# Microcontroller.net
KiCad netlist of a schematic drawn in Altium Designer
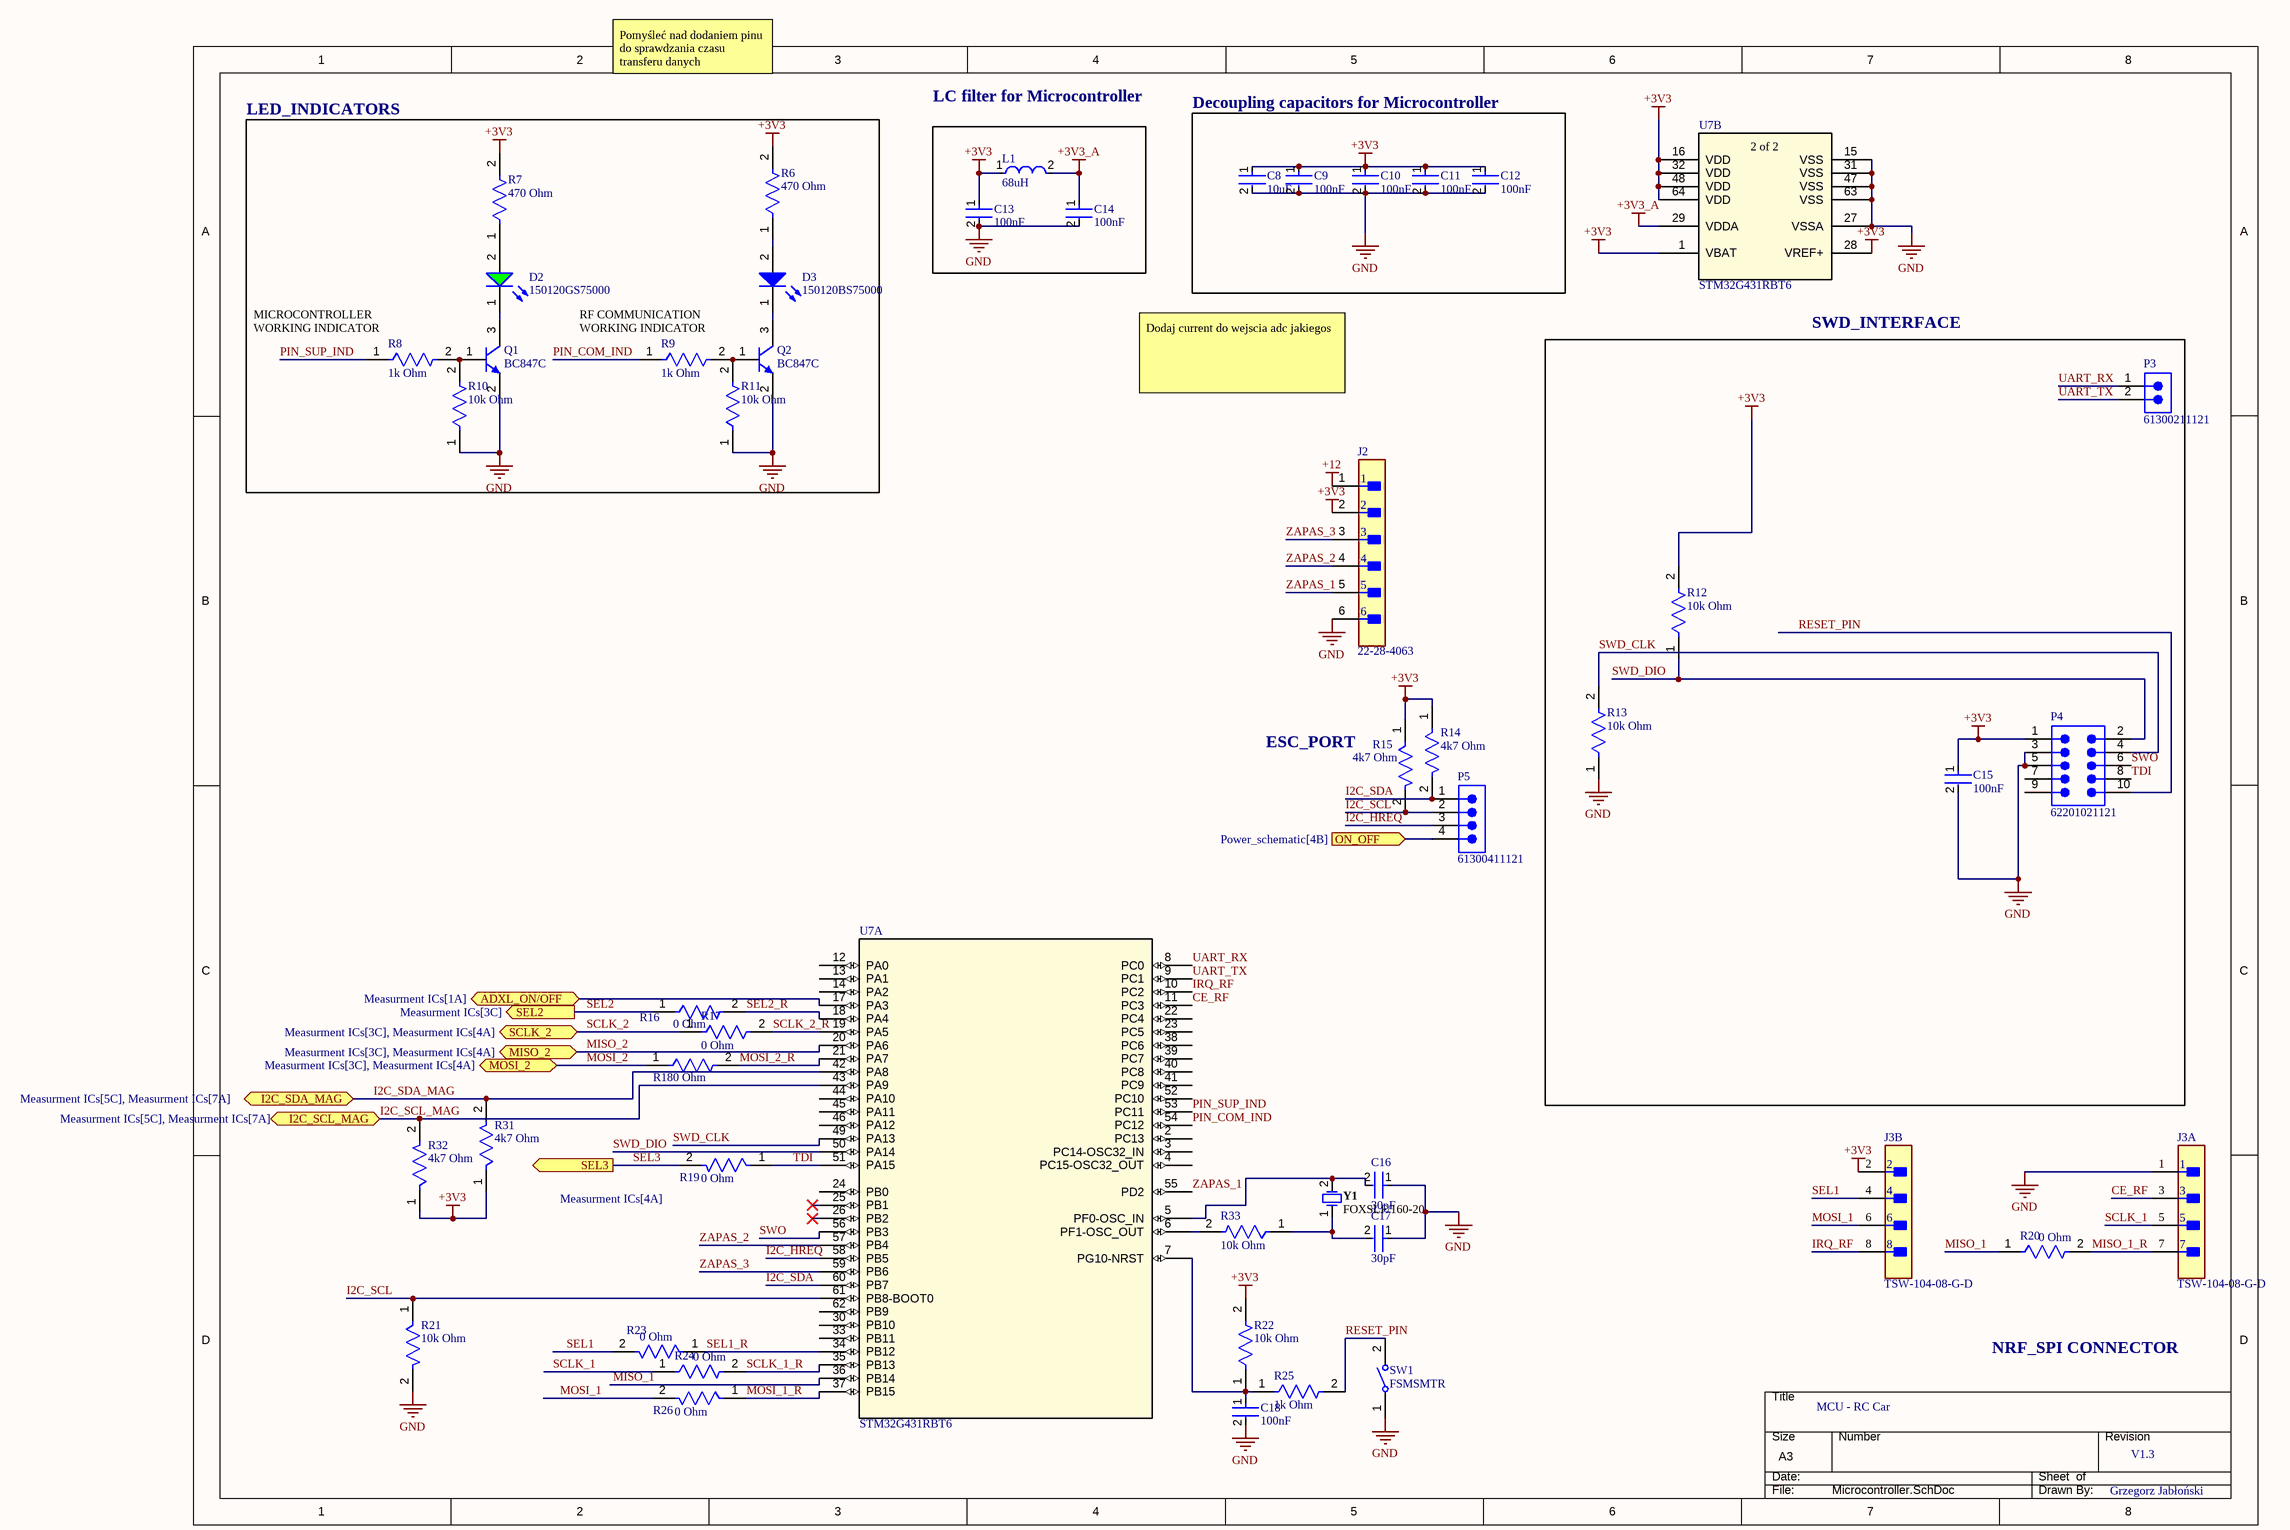
[diagram p0: Microcontroller.SchDoc]

(export (version "E")
  (design (tool "Eeschema 10.0.6"))
  (components
    (comp (ref "C8")
      (value "10uF")
      (footprint "FP-CC0805-0_85-MFG")
      (description "CAP CER 0.1UF 50V X7R 0805")
      (fields (field (name "TOLERANCE") "0.1") (field (name "MANUFACTURER PART NUMBER") "CC0805KRX7R9BB104"))
      (libsource (lib "Altium Content Vault") (part "11868f565c42a9108669ba33697ecf6"))
    )
    (comp (ref "C9")
      (value "100nF")
      (footprint "FP-CC0805-0_85-MFG")
      (description "CAP CER 0.1UF 50V X7R 0805")
      (fields (field (name "TOLERANCE") "0.1") (field (name "MANUFACTURER PART NUMBER") "CC0805KRX7R9BB104"))
      (libsource (lib "Altium Content Vault") (part "11868f565c42a9108669ba33697ecf6"))
    )
    (comp (ref "C10")
      (value "100nF")
      (footprint "FP-CC0805-0_85-MFG")
      (description "CAP CER 0.1UF 50V X7R 0805")
      (fields (field (name "TOLERANCE") "0.1") (field (name "MANUFACTURER PART NUMBER") "CC0805KRX7R9BB104"))
      (libsource (lib "Altium Content Vault") (part "11868f565c42a9108669ba33697ecf6"))
    )
    (comp (ref "C11")
      (value "100nF")
      (footprint "FP-CC0805-0_85-MFG")
      (description "CAP CER 0.1UF 50V X7R 0805")
      (fields (field (name "TOLERANCE") "0.1") (field (name "MANUFACTURER PART NUMBER") "CC0805KRX7R9BB104"))
      (libsource (lib "Altium Content Vault") (part "11868f565c42a9108669ba33697ecf6"))
    )
    (comp (ref "C12")
      (value "100nF")
      (footprint "FP-CC0805-0_85-MFG")
      (description "CAP CER 0.1UF 50V X7R 0805")
      (fields (field (name "TOLERANCE") "0.1") (field (name "MANUFACTURER PART NUMBER") "CC0805KRX7R9BB104"))
      (libsource (lib "Altium Content Vault") (part "11868f565c42a9108669ba33697ecf6"))
    )
    (comp (ref "C13")
      (value "100nF")
      (footprint "FP-CC0805-0_85-MFG")
      (description "CAP CER 0.1UF 50V X7R 0805")
      (fields (field (name "TOLERANCE") "0.1") (field (name "MANUFACTURER PART NUMBER") "CC0805KRX7R9BB104"))
      (libsource (lib "Altium Content Vault") (part "11868f565c42a9108669ba33697ecf6"))
    )
    (comp (ref "C14")
      (value "100nF")
      (footprint "FP-CC0805-0_85-MFG")
      (description "CAP CER 0.1UF 50V X7R 0805")
      (fields (field (name "TOLERANCE") "0.1") (field (name "MANUFACTURER PART NUMBER") "CC0805KRX7R9BB104"))
      (libsource (lib "Altium Content Vault") (part "11868f565c42a9108669ba33697ecf6"))
    )
    (comp (ref "C15")
      (value "100nF")
      (footprint "FP-CC0805-0_85-MFG")
      (description "CAP CER 0.1UF 50V X7R 0805")
      (fields (field (name "TOLERANCE") "0.1") (field (name "MANUFACTURER PART NUMBER") "CC0805KRX7R9BB104"))
      (libsource (lib "Altium Content Vault") (part "11868f565c42a9108669ba33697ecf6"))
    )
    (comp (ref "C16")
      (value "30pF")
      (footprint "FP-CC0805-0_85-MFG")
      (description "CAP CER 0.1UF 50V X7R 0805")
      (fields (field (name "TOLERANCE") "0.1") (field (name "MANUFACTURER PART NUMBER") "CC0805KRX7R9BB104"))
      (libsource (lib "Altium Content Vault") (part "11868f565c42a9108669ba33697ecf6"))
    )
    (comp (ref "C17")
      (value "30pF")
      (footprint "FP-CC0805-0_85-MFG")
      (description "CAP CER 0.1UF 50V X7R 0805")
      (fields (field (name "TOLERANCE") "0.1") (field (name "MANUFACTURER PART NUMBER") "CC0805KRX7R9BB104"))
      (libsource (lib "Altium Content Vault") (part "11868f565c42a9108669ba33697ecf6"))
    )
    (comp (ref "C18")
      (value "100nF")
      (footprint "FP-CC0805-0_85-MFG")
      (description "CAP CER 0.1UF 50V X7R 0805")
      (fields (field (name "TOLERANCE") "0.1") (field (name "MANUFACTURER PART NUMBER") "CC0805KRX7R9BB104"))
      (libsource (lib "Altium Content Vault") (part "11868f565c42a9108669ba33697ecf6"))
    )
    (comp (ref "D2")
      (value "150120GS75000")
      (footprint "WL-SMCW_1206_150120xx75000")
      (description "WL-SMCW SMT Mono-Color Chip LED Waterclear")
      (libsource (lib "Altium Content Vault") (part "LED_Green_2A-1K"))
    )
    (comp (ref "D3")
      (value "150120BS75000")
      (footprint "WL-SMCW_1206_150120xx75000")
      (description "WL-SMCW SMT Mono-Color Chip LED Waterclear")
      (libsource (lib "Altium Content Vault") (part "LED_Blue_2A-1K"))
    )
    (comp (ref "J2")
      (value "22-28-4063")
      (footprint "FP-22-28-4063-MFG")
      (description "CONN HEADER VERT 6POS 2.54MM")
      (libsource (lib "Altium Content Vault") (part "f2cb566baf1c37ab5a3b8e90bbeafd6"))
    )
    (comp (ref "J3")
      (value "TSW-104-08-G-D")
      (footprint "FP-TSW-104-08-G-D-MFG")
      (libsource (lib "Altium Content Vault") (part "811e954b9c034aa737de4d9295cbe7e"))
    )
    (comp (ref "L1")
      (value "68uH")
      (footprint "FP-CB2518-MFG")
      (description "SMD Inductors 68uH ±10% 0.31A 1.95Ω 1007")
      (fields (field (name "TOLERANCE") "10%"))
      (libsource (lib "Altium Content Vault") (part "725321dda6339637d4d059423bc1c3c"))
    )
    (comp (ref "P3")
      (value "61300211121")
      (footprint "61300211121")
      (libsource (lib "Altium Content Vault") (part "Header_Male_1R_02P"))
    )
    (comp (ref "P4")
      (value "62201021121")
      (footprint "62201021121")
      (libsource (lib "Altium Content Vault") (part "Header_Male_2R_10P"))
    )
    (comp (ref "P5")
      (value "61300411121")
      (footprint "61300411121")
      (libsource (lib "Altium Content Vault") (part "Header_Male_1R_04P"))
    )
    (comp (ref "Q1")
      (value "BC847C")
      (footprint "INF-SOT23_L")
      (description "NPN Silicon AF Transistor, 45 V VCEO, 100 mA IC, SOT23, Reel, Green")
      (fields (field (name "MANUFACTURER") "Infineon"))
      (libsource (lib "Altium Content Vault") (part "INF-BJTNPN-BEC-3"))
    )
    (comp (ref "Q2")
      (value "BC847C")
      (footprint "INF-SOT23_L")
      (description "NPN Silicon AF Transistor, 45 V VCEO, 100 mA IC, SOT23, Reel, Green")
      (fields (field (name "MANUFACTURER") "Infineon"))
      (libsource (lib "Altium Content Vault") (part "INF-BJTNPN-BEC-3"))
    )
    (comp (ref "R6")
      (value "470 Ohm")
      (footprint "FP-RMCF0805-MFG")
      (description "RES 0 OHM JUMPER 1/8W 0805")
      (libsource (lib "Altium Content Vault") (part "1029c3af85768c4190bb7ad29bc67b5"))
    )
    (comp (ref "R7")
      (value "470 Ohm")
      (footprint "FP-RMCF0805-MFG")
      (description "RES 0 OHM JUMPER 1/8W 0805")
      (libsource (lib "Altium Content Vault") (part "1029c3af85768c4190bb7ad29bc67b5"))
    )
    (comp (ref "R8")
      (value "1k Ohm")
      (footprint "FP-RMCF0805-MFG")
      (description "RES 0 OHM JUMPER 1/8W 0805")
      (libsource (lib "Altium Content Vault") (part "1029c3af85768c4190bb7ad29bc67b5"))
    )
    (comp (ref "R9")
      (value "1k Ohm")
      (footprint "FP-RMCF0805-MFG")
      (description "RES 0 OHM JUMPER 1/8W 0805")
      (libsource (lib "Altium Content Vault") (part "1029c3af85768c4190bb7ad29bc67b5"))
    )
    (comp (ref "R10")
      (value "10k Ohm")
      (footprint "FP-RMCF0805-MFG")
      (description "RES 0 OHM JUMPER 1/8W 0805")
      (libsource (lib "Altium Content Vault") (part "1029c3af85768c4190bb7ad29bc67b5"))
    )
    (comp (ref "R11")
      (value "10k Ohm")
      (footprint "FP-RMCF0805-MFG")
      (description "RES 0 OHM JUMPER 1/8W 0805")
      (libsource (lib "Altium Content Vault") (part "1029c3af85768c4190bb7ad29bc67b5"))
    )
    (comp (ref "R12")
      (value "10k Ohm")
      (footprint "FP-RMCF0805-MFG")
      (description "RES 0 OHM JUMPER 1/8W 0805")
      (libsource (lib "Altium Content Vault") (part "1029c3af85768c4190bb7ad29bc67b5"))
    )
    (comp (ref "R13")
      (value "10k Ohm")
      (footprint "FP-RMCF0805-MFG")
      (description "RES 0 OHM JUMPER 1/8W 0805")
      (libsource (lib "Altium Content Vault") (part "1029c3af85768c4190bb7ad29bc67b5"))
    )
    (comp (ref "R14")
      (value "4k7 Ohm")
      (footprint "FP-RMCF0805-MFG")
      (description "RES 0 OHM JUMPER 1/8W 0805")
      (libsource (lib "Altium Content Vault") (part "1029c3af85768c4190bb7ad29bc67b5"))
    )
    (comp (ref "R15")
      (value "4k7 Ohm")
      (footprint "FP-RMCF0805-MFG")
      (description "RES 0 OHM JUMPER 1/8W 0805")
      (libsource (lib "Altium Content Vault") (part "1029c3af85768c4190bb7ad29bc67b5"))
    )
    (comp (ref "R16")
      (value "0 Ohm")
      (footprint "FP-RMCF0805-MFG")
      (description "RES 0 OHM JUMPER 1/8W 0805")
      (libsource (lib "Altium Content Vault") (part "1029c3af85768c4190bb7ad29bc67b5"))
    )
    (comp (ref "R17")
      (value "0 Ohm")
      (footprint "FP-RMCF0805-MFG")
      (description "RES 0 OHM JUMPER 1/8W 0805")
      (libsource (lib "Altium Content Vault") (part "1029c3af85768c4190bb7ad29bc67b5"))
    )
    (comp (ref "R18")
      (value "0 Ohm")
      (footprint "FP-RMCF0805-MFG")
      (description "RES 0 OHM JUMPER 1/8W 0805")
      (libsource (lib "Altium Content Vault") (part "1029c3af85768c4190bb7ad29bc67b5"))
    )
    (comp (ref "R19")
      (value "0 Ohm")
      (footprint "FP-RMCF0805-MFG")
      (description "RES 0 OHM JUMPER 1/8W 0805")
      (libsource (lib "Altium Content Vault") (part "1029c3af85768c4190bb7ad29bc67b5"))
    )
    (comp (ref "R20")
      (value "0 Ohm")
      (footprint "FP-RMCF0805-MFG")
      (description "RES 0 OHM JUMPER 1/8W 0805")
      (libsource (lib "Altium Content Vault") (part "1029c3af85768c4190bb7ad29bc67b5"))
    )
    (comp (ref "R21")
      (value "10k Ohm")
      (footprint "FP-RMCF0805-MFG")
      (description "RES 0 OHM JUMPER 1/8W 0805")
      (libsource (lib "Altium Content Vault") (part "1029c3af85768c4190bb7ad29bc67b5"))
    )
    (comp (ref "R22")
      (value "10k Ohm")
      (footprint "FP-RMCF0805-MFG")
      (description "RES 0 OHM JUMPER 1/8W 0805")
      (libsource (lib "Altium Content Vault") (part "1029c3af85768c4190bb7ad29bc67b5"))
    )
    (comp (ref "R23")
      (value "0 Ohm")
      (footprint "FP-RMCF0805-MFG")
      (description "RES 0 OHM JUMPER 1/8W 0805")
      (libsource (lib "Altium Content Vault") (part "1029c3af85768c4190bb7ad29bc67b5"))
    )
    (comp (ref "R24")
      (value "0 Ohm")
      (footprint "FP-RMCF0805-MFG")
      (description "RES 0 OHM JUMPER 1/8W 0805")
      (libsource (lib "Altium Content Vault") (part "1029c3af85768c4190bb7ad29bc67b5"))
    )
    (comp (ref "R25")
      (value "1k Ohm")
      (footprint "FP-RMCF0805-MFG")
      (description "RES 0 OHM JUMPER 1/8W 0805")
      (libsource (lib "Altium Content Vault") (part "1029c3af85768c4190bb7ad29bc67b5"))
    )
    (comp (ref "R26")
      (value "0 Ohm")
      (footprint "FP-RMCF0805-MFG")
      (description "RES 0 OHM JUMPER 1/8W 0805")
      (libsource (lib "Altium Content Vault") (part "1029c3af85768c4190bb7ad29bc67b5"))
    )
    (comp (ref "R31")
      (value "4k7 Ohm")
      (footprint "FP-RMCF0805-MFG")
      (description "RES 0 OHM JUMPER 1/8W 0805")
      (libsource (lib "Altium Content Vault") (part "1029c3af85768c4190bb7ad29bc67b5"))
    )
    (comp (ref "R32")
      (value "4k7 Ohm")
      (footprint "FP-RMCF0805-MFG")
      (description "RES 0 OHM JUMPER 1/8W 0805")
      (libsource (lib "Altium Content Vault") (part "1029c3af85768c4190bb7ad29bc67b5"))
    )
    (comp (ref "R33")
      (value "10k Ohm")
      (footprint "FP-RMCF0805-MFG")
      (description "RES 0 OHM JUMPER 1/8W 0805")
      (libsource (lib "Altium Content Vault") (part "1029c3af85768c4190bb7ad29bc67b5"))
    )
    (comp (ref "SW1")
      (value "FSMSMTR")
      (footprint "TECO-FSMSMTR_V")
      (description "FSMSM Push Button Switch, 50 mA, -35 to 85 degC, 2-Pin SMD, RoHS, Tape and Reel")
      (fields (field (name "MANUFACTURER") "TE Connectivity"))
      (libsource (lib "Altium Content Vault") (part "SW-SPST-2_C"))
    )
    (comp (ref "U7")
      (value "STM32G431RBT6")
      (footprint "LQFP64-10x10mm")
      (description "No Description Available")
      (libsource (lib "STM32G431RBT6") (part "STM32G431RBT6"))
    )
    (comp (ref "Y1")
      (value "FOXSLF/160-20")
      (footprint "FOX-FOXSLF160-20")
      (description "Resistance Weld Thru-Hole Crystal, 16 MHz, -20 to 70 degC, 2-Pin THD, RoHS, Bulk")
      (fields (field (name "TOLERANCE") "1%"))
      (libsource (lib "Altium Content Vault") (part "XTAL-1-2-2"))
    )
  )
  (nets
    (net (code "1") (name "+3V3") (class "Default")
      (node (ref "C10") (pin "1") (pinfunction "1_1") (pintype "passive"))
      (node (ref "C11") (pin "1") (pinfunction "1_1") (pintype "passive"))
      (node (ref "C12") (pin "1") (pinfunction "1_1") (pintype "passive"))
      (node (ref "C13") (pin "1") (pinfunction "1_1") (pintype "passive"))
      (node (ref "C15") (pin "1") (pinfunction "1_1") (pintype "passive"))
      (node (ref "C8") (pin "1") (pinfunction "1_1") (pintype "passive"))
      (node (ref "C9") (pin "1") (pinfunction "1_1") (pintype "passive"))
      (node (ref "J2") (pin "2") (pinfunction "2_2") (pintype "passive"))
      (node (ref "J3") (pin "2") (pinfunction "2_2") (pintype "passive"))
      (node (ref "L1") (pin "1") (pinfunction "1_1") (pintype "passive"))
      (node (ref "P4") (pin "1") (pinfunction "1_1") (pintype "passive"))
      (node (ref "R12") (pin "2") (pinfunction "2_2") (pintype "passive"))
      (node (ref "R14") (pin "1") (pinfunction "1_1") (pintype "passive"))
      (node (ref "R15") (pin "1") (pinfunction "1_1") (pintype "passive"))
      (node (ref "R22") (pin "2") (pinfunction "2_2") (pintype "passive"))
      (node (ref "R31") (pin "1") (pinfunction "1_1") (pintype "passive"))
      (node (ref "R32") (pin "1") (pinfunction "1_1") (pintype "passive"))
      (node (ref "R6") (pin "2") (pinfunction "2_2") (pintype "passive"))
      (node (ref "R7") (pin "2") (pinfunction "2_2") (pintype "passive"))
      (node (ref "U7") (pin "1") (pinfunction "VBAT_1") (pintype "power_in"))
      (node (ref "U7") (pin "16") (pinfunction "VDD_16") (pintype "power_in"))
      (node (ref "U7") (pin "28") (pinfunction "VREF+_28") (pintype "power_in"))
      (node (ref "U7") (pin "32") (pinfunction "VDD_32") (pintype "power_in"))
      (node (ref "U7") (pin "48") (pinfunction "VDD_48") (pintype "power_in"))
      (node (ref "U7") (pin "64") (pinfunction "VDD_64") (pintype "power_in"))
    )
    (net (code "2") (name "+3V3_A") (class "Default")
      (node (ref "C14") (pin "1") (pinfunction "1_1") (pintype "passive"))
      (node (ref "L1") (pin "2") (pinfunction "2_2") (pintype "passive"))
      (node (ref "U7") (pin "29") (pinfunction "VDDA_29") (pintype "power_in"))
    )
    (net (code "3") (name "+12") (class "Default")
      (node (ref "J2") (pin "1") (pinfunction "1_1") (pintype "passive"))
    )
    (net (code "4") (name "/ADXL_ON{slash}OFF") (class "Default")
      (node (ref "U7") (pin "17") (pinfunction "PA3_17") (pintype "bidirectional"))
    )
    (net (code "5") (name "/CE_RF") (class "Default")
      (node (ref "J3") (pin "3") (pinfunction "3_3") (pintype "passive"))
      (node (ref "U7") (pin "11") (pinfunction "PC3_11") (pintype "bidirectional"))
    )
    (net (code "6") (name "/I2C_HREQ") (class "Default")
      (node (ref "P5") (pin "3") (pinfunction "3_3") (pintype "passive"))
      (node (ref "U7") (pin "58") (pinfunction "PB5_58") (pintype "bidirectional"))
    )
    (net (code "7") (name "/I2C_SCL") (class "Default")
      (node (ref "P5") (pin "2") (pinfunction "2_2") (pintype "passive"))
      (node (ref "R15") (pin "2") (pinfunction "2_2") (pintype "passive"))
      (node (ref "R21") (pin "1") (pinfunction "1_1") (pintype "passive"))
      (node (ref "U7") (pin "61") (pinfunction "PB8-BOOT0_61") (pintype "bidirectional"))
    )
    (net (code "8") (name "/I2C_SCL_MAG") (class "Default")
      (node (ref "R32") (pin "2") (pinfunction "2_2") (pintype "passive"))
      (node (ref "U7") (pin "43") (pinfunction "PA9_43") (pintype "bidirectional"))
    )
    (net (code "9") (name "/I2C_SDA") (class "Default")
      (node (ref "P5") (pin "1") (pinfunction "1_1") (pintype "passive"))
      (node (ref "R14") (pin "2") (pinfunction "2_2") (pintype "passive"))
      (node (ref "U7") (pin "60") (pinfunction "PB7_60") (pintype "bidirectional"))
    )
    (net (code "10") (name "/I2C_SDA_MAG") (class "Default")
      (node (ref "R31") (pin "2") (pinfunction "2_2") (pintype "passive"))
      (node (ref "U7") (pin "42") (pinfunction "PA8_42") (pintype "bidirectional"))
    )
    (net (code "11") (name "/IRQ_RF") (class "Default")
      (node (ref "J3") (pin "8") (pinfunction "8_8") (pintype "passive"))
      (node (ref "U7") (pin "10") (pinfunction "PC2_10") (pintype "bidirectional"))
    )
    (net (code "12") (name "/MISO_1") (class "Default")
      (node (ref "R20") (pin "1") (pinfunction "1_1") (pintype "passive"))
      (node (ref "U7") (pin "36") (pinfunction "PB14_36") (pintype "bidirectional"))
    )
    (net (code "13") (name "/MISO_1_R") (class "Default")
      (node (ref "J3") (pin "7") (pinfunction "7_7") (pintype "passive"))
      (node (ref "R20") (pin "2") (pinfunction "2_2") (pintype "passive"))
    )
    (net (code "14") (name "/MISO_2") (class "Default")
      (node (ref "U7") (pin "20") (pinfunction "PA6_20") (pintype "bidirectional"))
    )
    (net (code "15") (name "/MOSI_1") (class "Default")
      (node (ref "J3") (pin "6") (pinfunction "6_6") (pintype "passive"))
      (node (ref "R26") (pin "2") (pinfunction "2_2") (pintype "passive"))
    )
    (net (code "16") (name "/MOSI_1_R") (class "Default")
      (node (ref "R26") (pin "1") (pinfunction "1_1") (pintype "passive"))
      (node (ref "U7") (pin "37") (pinfunction "PB15_37") (pintype "bidirectional"))
    )
    (net (code "17") (name "/MOSI_2") (class "Default")
      (node (ref "R18") (pin "1") (pinfunction "1_1") (pintype "passive"))
    )
    (net (code "18") (name "/MOSI_2_R") (class "Default")
      (node (ref "R18") (pin "2") (pinfunction "2_2") (pintype "passive"))
      (node (ref "U7") (pin "21") (pinfunction "PA7_21") (pintype "bidirectional"))
    )
    (net (code "19") (name "/ON_OFF") (class "Default")
      (node (ref "P5") (pin "4") (pinfunction "4_4") (pintype "passive"))
    )
    (net (code "20") (name "/PIN_COM_IND") (class "Default")
      (node (ref "R9") (pin "1") (pinfunction "1_1") (pintype "passive"))
      (node (ref "U7") (pin "54") (pinfunction "PC12_54") (pintype "bidirectional"))
    )
    (net (code "21") (name "/PIN_SUP_IND") (class "Default")
      (node (ref "R8") (pin "1") (pinfunction "1_1") (pintype "passive"))
      (node (ref "U7") (pin "53") (pinfunction "PC11_53") (pintype "bidirectional"))
    )
    (net (code "22") (name "/RESET_PIN") (class "Default")
      (node (ref "P4") (pin "10") (pinfunction "10_10") (pintype "passive"))
      (node (ref "R25") (pin "2") (pinfunction "2_2") (pintype "passive"))
      (node (ref "SW1") (pin "2") (pinfunction "2_2") (pintype "passive"))
    )
    (net (code "23") (name "/SCLK_1") (class "Default")
      (node (ref "J3") (pin "5") (pinfunction "5_5") (pintype "passive"))
      (node (ref "R24") (pin "1") (pinfunction "1_1") (pintype "passive"))
    )
    (net (code "24") (name "/SCLK_1_R") (class "Default")
      (node (ref "R24") (pin "2") (pinfunction "2_2") (pintype "passive"))
      (node (ref "U7") (pin "35") (pinfunction "PB13_35") (pintype "bidirectional"))
    )
    (net (code "25") (name "/SCLK_2") (class "Default")
      (node (ref "R17") (pin "1") (pinfunction "1_1") (pintype "passive"))
    )
    (net (code "26") (name "/SCLK_2_R") (class "Default")
      (node (ref "R17") (pin "2") (pinfunction "2_2") (pintype "passive"))
      (node (ref "U7") (pin "19") (pinfunction "PA5_19") (pintype "bidirectional"))
    )
    (net (code "27") (name "/SEL1") (class "Default")
      (node (ref "J3") (pin "4") (pinfunction "4_4") (pintype "passive"))
      (node (ref "R23") (pin "2") (pinfunction "2_2") (pintype "passive"))
    )
    (net (code "28") (name "/SEL1_R") (class "Default")
      (node (ref "R23") (pin "1") (pinfunction "1_1") (pintype "passive"))
      (node (ref "U7") (pin "34") (pinfunction "PB12_34") (pintype "bidirectional"))
    )
    (net (code "29") (name "/SEL2") (class "Default")
      (node (ref "R16") (pin "1") (pinfunction "1_1") (pintype "passive"))
    )
    (net (code "30") (name "/SEL2_R") (class "Default")
      (node (ref "R16") (pin "2") (pinfunction "2_2") (pintype "passive"))
      (node (ref "U7") (pin "18") (pinfunction "PA4_18") (pintype "bidirectional"))
    )
    (net (code "31") (name "/SEL3") (class "Default")
      (node (ref "R19") (pin "2") (pinfunction "2_2") (pintype "passive"))
    )
    (net (code "32") (name "/SWD_CLK") (class "Default")
      (node (ref "P4") (pin "4") (pinfunction "4_4") (pintype "passive"))
      (node (ref "R13") (pin "2") (pinfunction "2_2") (pintype "passive"))
      (node (ref "U7") (pin "49") (pinfunction "PA13_49") (pintype "bidirectional"))
    )
    (net (code "33") (name "/SWD_DIO") (class "Default")
      (node (ref "P4") (pin "2") (pinfunction "2_2") (pintype "passive"))
      (node (ref "R12") (pin "1") (pinfunction "1_1") (pintype "passive"))
      (node (ref "U7") (pin "50") (pinfunction "PA14_50") (pintype "bidirectional"))
    )
    (net (code "34") (name "/SWO") (class "Default")
      (node (ref "P4") (pin "6") (pinfunction "6_6") (pintype "passive"))
      (node (ref "U7") (pin "56") (pinfunction "PB3_56") (pintype "bidirectional"))
    )
    (net (code "35") (name "/TDI") (class "Default")
      (node (ref "P4") (pin "8") (pinfunction "8_8") (pintype "passive"))
      (node (ref "R19") (pin "1") (pinfunction "1_1") (pintype "passive"))
      (node (ref "U7") (pin "51") (pinfunction "PA15_51") (pintype "bidirectional"))
    )
    (net (code "36") (name "/UART_RX") (class "Default")
      (node (ref "P3") (pin "1") (pinfunction "1_1") (pintype "passive"))
      (node (ref "U7") (pin "8") (pinfunction "PC0_8") (pintype "bidirectional"))
    )
    (net (code "37") (name "/UART_TX") (class "Default")
      (node (ref "P3") (pin "2") (pinfunction "2_2") (pintype "passive"))
      (node (ref "U7") (pin "9") (pinfunction "PC1_9") (pintype "bidirectional"))
    )
    (net (code "38") (name "/ZAPAS_1") (class "Default")
      (node (ref "J2") (pin "5") (pinfunction "5_5") (pintype "passive"))
      (node (ref "U7") (pin "55") (pinfunction "PD2_55") (pintype "bidirectional"))
    )
    (net (code "39") (name "/ZAPAS_2") (class "Default")
      (node (ref "J2") (pin "4") (pinfunction "4_4") (pintype "passive"))
      (node (ref "U7") (pin "57") (pinfunction "PB4_57") (pintype "bidirectional"))
    )
    (net (code "40") (name "/ZAPAS_3") (class "Default")
      (node (ref "J2") (pin "3") (pinfunction "3_3") (pintype "passive"))
      (node (ref "U7") (pin "59") (pinfunction "PB6_59") (pintype "bidirectional"))
    )
    (net (code "41") (name "GND") (class "Default")
      (node (ref "C10") (pin "2") (pinfunction "2_2") (pintype "passive"))
      (node (ref "C11") (pin "2") (pinfunction "2_2") (pintype "passive"))
      (node (ref "C12") (pin "2") (pinfunction "2_2") (pintype "passive"))
      (node (ref "C13") (pin "2") (pinfunction "2_2") (pintype "passive"))
      (node (ref "C14") (pin "2") (pinfunction "2_2") (pintype "passive"))
      (node (ref "C15") (pin "2") (pinfunction "2_2") (pintype "passive"))
      (node (ref "C16") (pin "1") (pinfunction "1_1") (pintype "passive"))
      (node (ref "C17") (pin "1") (pinfunction "1_1") (pintype "passive"))
      (node (ref "C18") (pin "2") (pinfunction "2_2") (pintype "passive"))
      (node (ref "C8") (pin "2") (pinfunction "2_2") (pintype "passive"))
      (node (ref "C9") (pin "2") (pinfunction "2_2") (pintype "passive"))
      (node (ref "J2") (pin "6") (pinfunction "6_6") (pintype "passive"))
      (node (ref "J3") (pin "1") (pinfunction "1_1") (pintype "passive"))
      (node (ref "P4") (pin "3") (pinfunction "3_3") (pintype "passive"))
      (node (ref "P4") (pin "5") (pinfunction "5_5") (pintype "passive"))
      (node (ref "Q1") (pin "2") (pinfunction "E_2") (pintype "passive"))
      (node (ref "Q2") (pin "2") (pinfunction "E_2") (pintype "passive"))
      (node (ref "R10") (pin "1") (pinfunction "1_1") (pintype "passive"))
      (node (ref "R11") (pin "1") (pinfunction "1_1") (pintype "passive"))
      (node (ref "R13") (pin "1") (pinfunction "1_1") (pintype "passive"))
      (node (ref "R21") (pin "2") (pinfunction "2_2") (pintype "passive"))
      (node (ref "SW1") (pin "1") (pinfunction "1_1") (pintype "passive"))
      (node (ref "U7") (pin "15") (pinfunction "VSS_15") (pintype "power_in"))
      (node (ref "U7") (pin "27") (pinfunction "VSSA_27") (pintype "power_in"))
      (node (ref "U7") (pin "31") (pinfunction "VSS_31") (pintype "power_in"))
      (node (ref "U7") (pin "47") (pinfunction "VSS_47") (pintype "power_in"))
      (node (ref "U7") (pin "63") (pinfunction "VSS_63") (pintype "power_in"))
    )
    (net (code "42") (name "Net-(C17-Pad2)") (class "Default")
      (node (ref "C17") (pin "2") (pinfunction "2_2") (pintype "passive"))
      (node (ref "R33") (pin "1") (pinfunction "1_1") (pintype "passive"))
      (node (ref "Y1") (pin "1") (pinfunction "1_1") (pintype "passive"))
    )
    (net (code "43") (name "Net-(D2-A)") (class "Default")
      (node (ref "D2") (pin "2") (pinfunction "A_2") (pintype "passive"))
      (node (ref "R7") (pin "1") (pinfunction "1_1") (pintype "passive"))
    )
    (net (code "44") (name "Net-(D2-K)") (class "Default")
      (node (ref "D2") (pin "1") (pinfunction "K_1") (pintype "passive"))
      (node (ref "Q1") (pin "3") (pinfunction "C_3") (pintype "passive"))
    )
    (net (code "45") (name "Net-(D3-A)") (class "Default")
      (node (ref "D3") (pin "2") (pinfunction "A_2") (pintype "passive"))
      (node (ref "R6") (pin "1") (pinfunction "1_1") (pintype "passive"))
    )
    (net (code "46") (name "Net-(D3-K)") (class "Default")
      (node (ref "D3") (pin "1") (pinfunction "K_1") (pintype "passive"))
      (node (ref "Q2") (pin "3") (pinfunction "C_3") (pintype "passive"))
    )
    (net (code "47") (name "Net-(Q1-B)") (class "Default")
      (node (ref "Q1") (pin "1") (pinfunction "B_1") (pintype "passive"))
      (node (ref "R10") (pin "2") (pinfunction "2_2") (pintype "passive"))
      (node (ref "R8") (pin "2") (pinfunction "2_2") (pintype "passive"))
    )
    (net (code "48") (name "Net-(Q2-B)") (class "Default")
      (node (ref "Q2") (pin "1") (pinfunction "B_1") (pintype "passive"))
      (node (ref "R11") (pin "2") (pinfunction "2_2") (pintype "passive"))
      (node (ref "R9") (pin "2") (pinfunction "2_2") (pintype "passive"))
    )
    (net (code "49") (name "Net-(U7A-PF0-OSC_IN)") (class "Default")
      (node (ref "C16") (pin "2") (pinfunction "2_2") (pintype "passive"))
      (node (ref "U7") (pin "5") (pinfunction "PF0-OSC_IN_5") (pintype "bidirectional"))
      (node (ref "Y1") (pin "2") (pinfunction "2_2") (pintype "passive"))
    )
    (net (code "50") (name "Net-(U7A-PF1-OSC_OUT)") (class "Default")
      (node (ref "R33") (pin "2") (pinfunction "2_2") (pintype "passive"))
      (node (ref "U7") (pin "6") (pinfunction "PF1-OSC_OUT_6") (pintype "bidirectional"))
    )
    (net (code "51") (name "Net-(U7A-PG10-NRST)") (class "Default")
      (node (ref "C18") (pin "1") (pinfunction "1_1") (pintype "passive"))
      (node (ref "R22") (pin "1") (pinfunction "1_1") (pintype "passive"))
      (node (ref "R25") (pin "1") (pinfunction "1_1") (pintype "passive"))
      (node (ref "U7") (pin "7") (pinfunction "PG10-NRST_7") (pintype "bidirectional"))
    )
    (net (code "52") (name "unconnected-(P4-Pad7)") (class "Default")
      (node (ref "P4") (pin "7") (pinfunction "7_7") (pintype "passive"))
    )
    (net (code "53") (name "unconnected-(P4-Pad9)") (class "Default")
      (node (ref "P4") (pin "9") (pinfunction "9_9") (pintype "passive"))
    )
    (net (code "54") (name "unconnected-(U7A-PA0-Pad12)") (class "Default")
      (node (ref "U7") (pin "12") (pinfunction "PA0_12") (pintype "bidirectional"))
    )
    (net (code "55") (name "unconnected-(U7A-PA1-Pad13)") (class "Default")
      (node (ref "U7") (pin "13") (pinfunction "PA1_13") (pintype "bidirectional"))
    )
    (net (code "56") (name "unconnected-(U7A-PA2-Pad14)") (class "Default")
      (node (ref "U7") (pin "14") (pinfunction "PA2_14") (pintype "bidirectional"))
    )
    (net (code "57") (name "unconnected-(U7A-PA10-Pad44)") (class "Default")
      (node (ref "U7") (pin "44") (pinfunction "PA10_44") (pintype "bidirectional"))
    )
    (net (code "58") (name "unconnected-(U7A-PA11-Pad45)") (class "Default")
      (node (ref "U7") (pin "45") (pinfunction "PA11_45") (pintype "bidirectional"))
    )
    (net (code "59") (name "unconnected-(U7A-PA12-Pad46)") (class "Default")
      (node (ref "U7") (pin "46") (pinfunction "PA12_46") (pintype "bidirectional"))
    )
    (net (code "60") (name "unconnected-(U7A-PB0-Pad24)") (class "Default")
      (node (ref "U7") (pin "24") (pinfunction "PB0_24") (pintype "bidirectional"))
    )
    (net (code "61") (name "unconnected-(U7A-PB1-Pad25)") (class "Default")
      (node (ref "U7") (pin "25") (pinfunction "PB1_25") (pintype "bidirectional+no_connect"))
    )
    (net (code "62") (name "unconnected-(U7A-PB2-Pad26)") (class "Default")
      (node (ref "U7") (pin "26") (pinfunction "PB2_26") (pintype "bidirectional+no_connect"))
    )
    (net (code "63") (name "unconnected-(U7A-PB9-Pad62)") (class "Default")
      (node (ref "U7") (pin "62") (pinfunction "PB9_62") (pintype "bidirectional"))
    )
    (net (code "64") (name "unconnected-(U7A-PB10-Pad30)") (class "Default")
      (node (ref "U7") (pin "30") (pinfunction "PB10_30") (pintype "bidirectional"))
    )
    (net (code "65") (name "unconnected-(U7A-PB11-Pad33)") (class "Default")
      (node (ref "U7") (pin "33") (pinfunction "PB11_33") (pintype "bidirectional"))
    )
    (net (code "66") (name "unconnected-(U7A-PC4-Pad22)") (class "Default")
      (node (ref "U7") (pin "22") (pinfunction "PC4_22") (pintype "bidirectional"))
    )
    (net (code "67") (name "unconnected-(U7A-PC5-Pad23)") (class "Default")
      (node (ref "U7") (pin "23") (pinfunction "PC5_23") (pintype "bidirectional"))
    )
    (net (code "68") (name "unconnected-(U7A-PC6-Pad38)") (class "Default")
      (node (ref "U7") (pin "38") (pinfunction "PC6_38") (pintype "bidirectional"))
    )
    (net (code "69") (name "unconnected-(U7A-PC7-Pad39)") (class "Default")
      (node (ref "U7") (pin "39") (pinfunction "PC7_39") (pintype "bidirectional"))
    )
    (net (code "70") (name "unconnected-(U7A-PC8-Pad40)") (class "Default")
      (node (ref "U7") (pin "40") (pinfunction "PC8_40") (pintype "bidirectional"))
    )
    (net (code "71") (name "unconnected-(U7A-PC9-Pad41)") (class "Default")
      (node (ref "U7") (pin "41") (pinfunction "PC9_41") (pintype "bidirectional"))
    )
    (net (code "72") (name "unconnected-(U7A-PC10-Pad52)") (class "Default")
      (node (ref "U7") (pin "52") (pinfunction "PC10_52") (pintype "bidirectional"))
    )
    (net (code "73") (name "unconnected-(U7A-PC13-Pad2)") (class "Default")
      (node (ref "U7") (pin "2") (pinfunction "PC13_2") (pintype "bidirectional"))
    )
    (net (code "74") (name "unconnected-(U7A-PC14-OSC32_IN-Pad3)") (class "Default")
      (node (ref "U7") (pin "3") (pinfunction "PC14-OSC32_IN_3") (pintype "bidirectional"))
    )
    (net (code "75") (name "unconnected-(U7A-PC15-OSC32_OUT-Pad4)") (class "Default")
      (node (ref "U7") (pin "4") (pinfunction "PC15-OSC32_OUT_4") (pintype "bidirectional"))
    )
  )
)
